# PCB-print.net
KiCad netlist of a schematic drawn in EasyEDA Pro
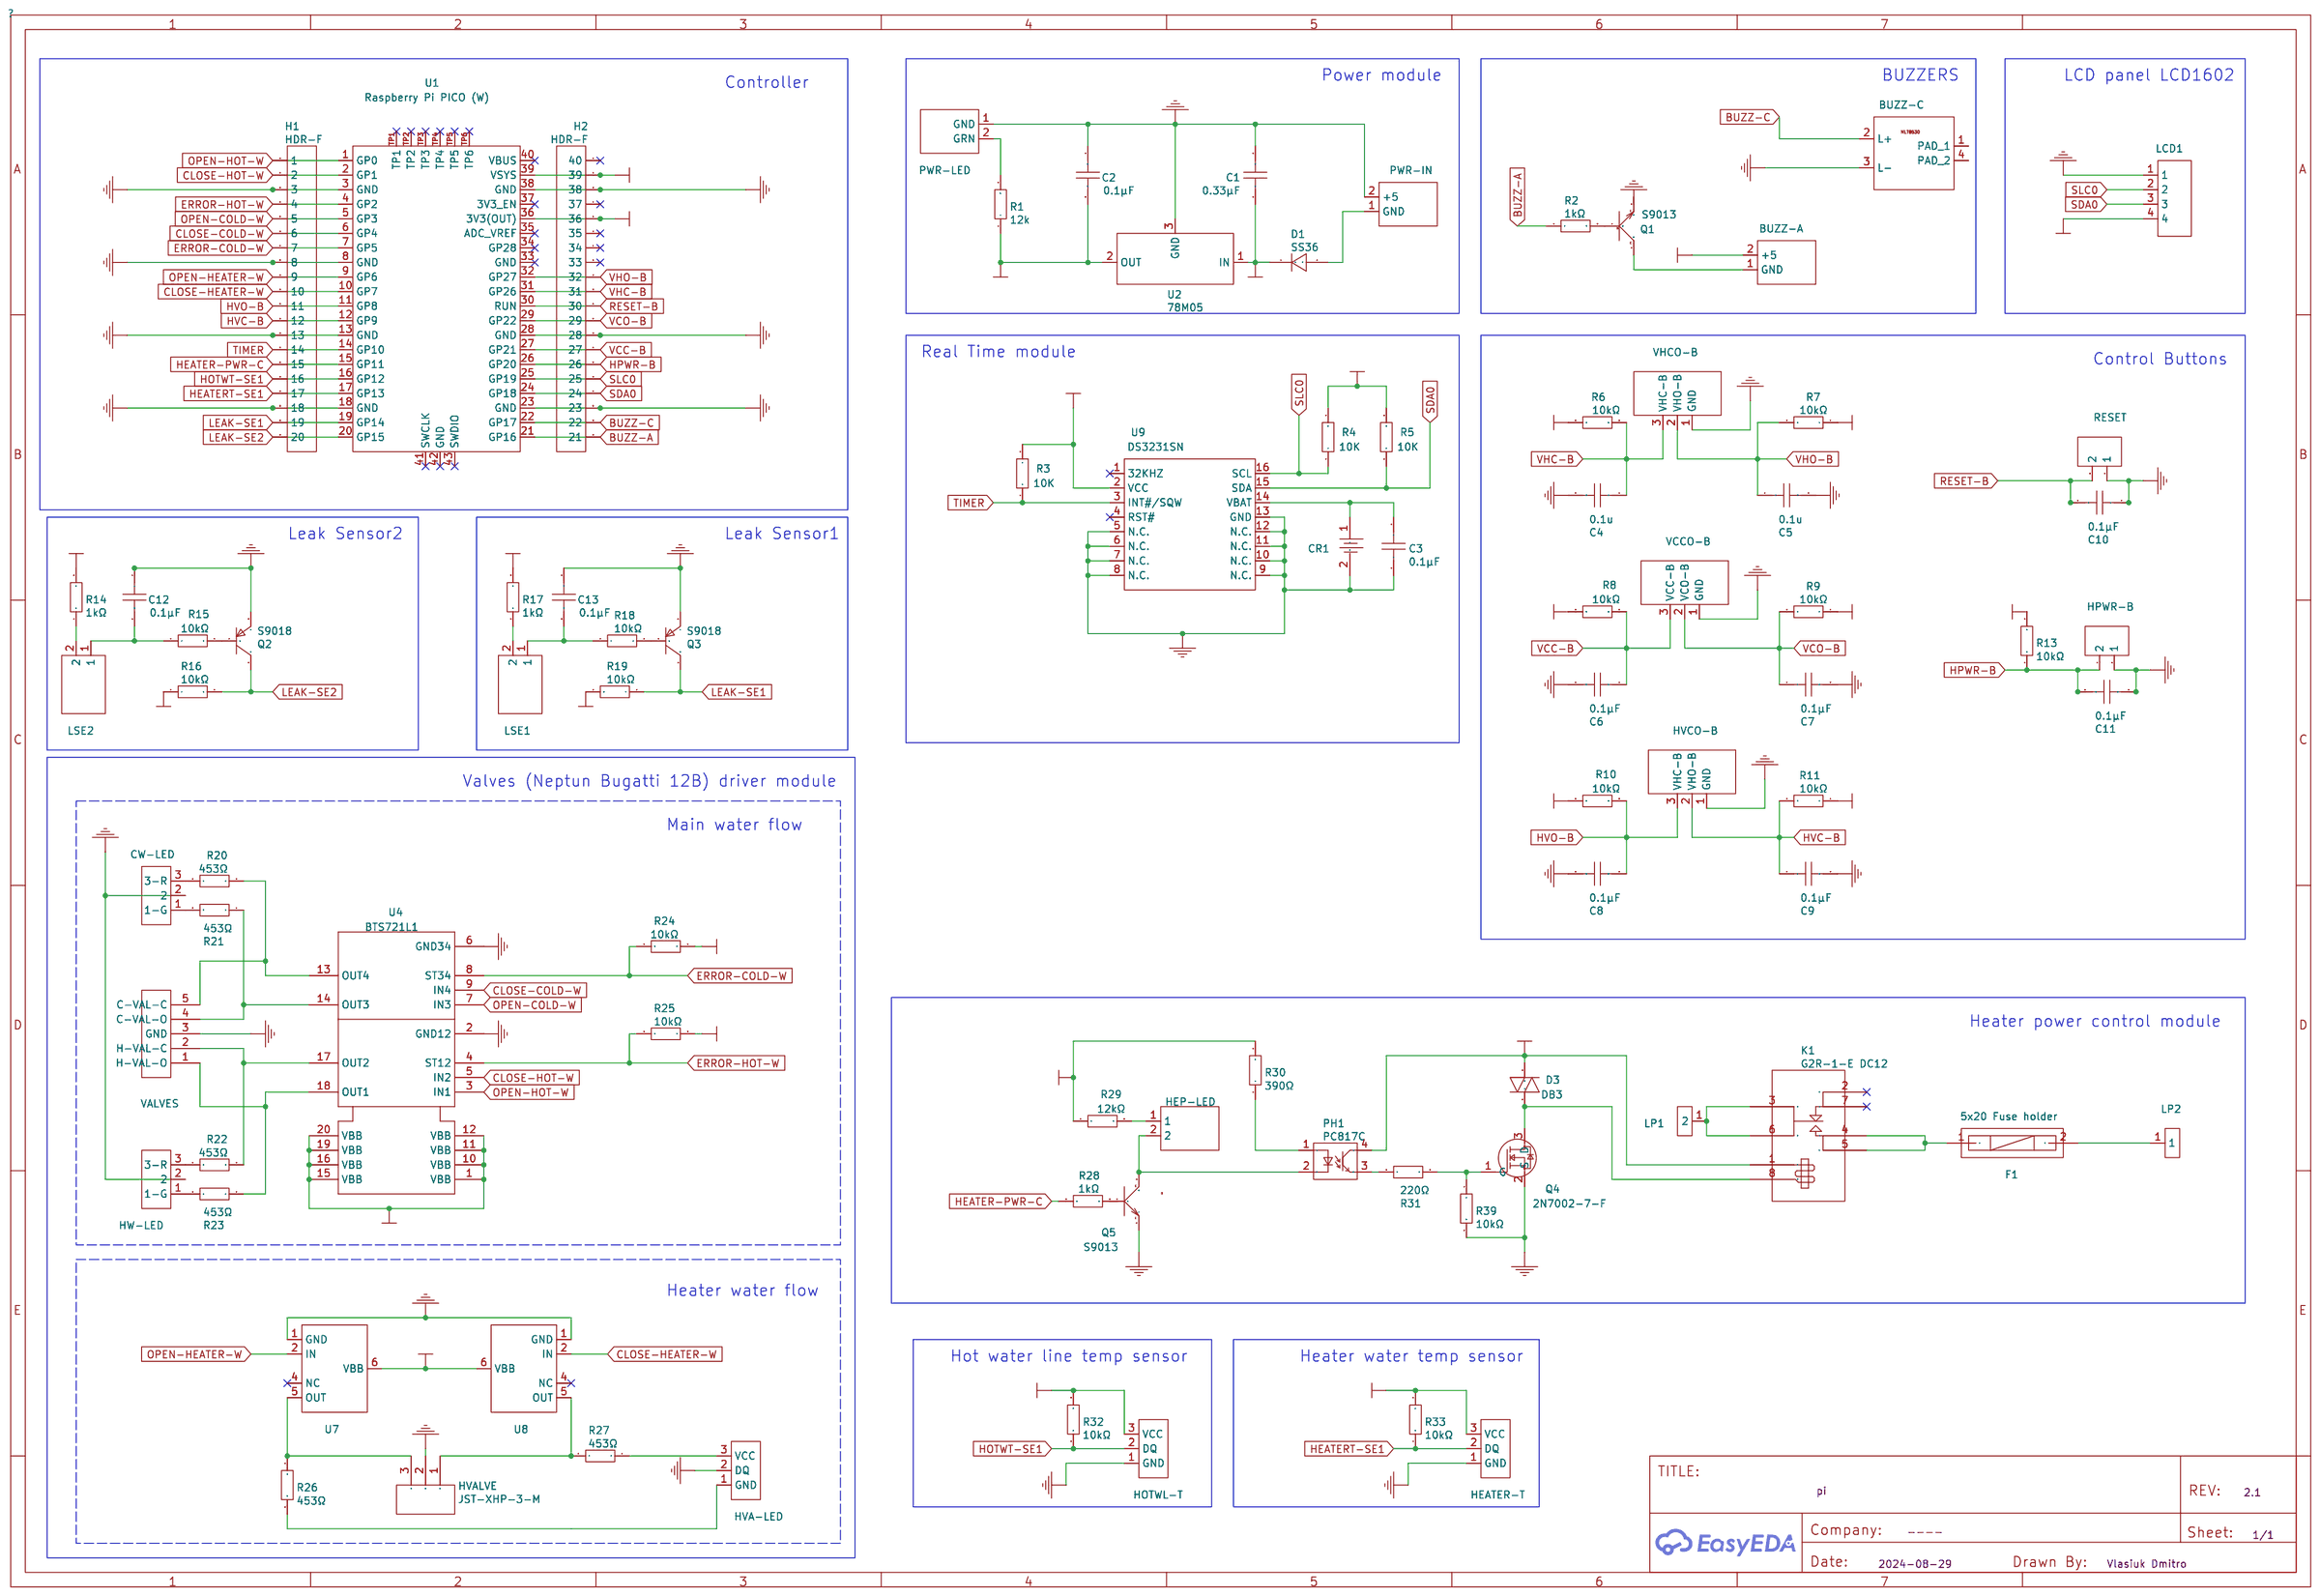
[diagram p0: schematic sheet]

(export (version "E")
  (design (tool "Eeschema 10.0.6"))
  (components
    (comp (ref "BUZZ-A")
      (value "KF2510")
      (fields (field (name "Contributor") "ryan.yulianto"))
      (libsource (lib "easyedapro") (part "KF2510"))
    )
    (comp (ref "BUZZ-C")
      (value "BUZZER-MLT8580_MLT-8530")
      (fields (field (name "Contributor") "Paul Walker"))
      (libsource (lib "easyedapro") (part "BUZZER-MLT8580_MLT-8530"))
    )
    (comp (ref "C1")
      (value "0.33μF")
      (fields (field (name "Manufacturer Part") "C0805X104K050T") (field (name "Contributor") "LCSC"))
      (libsource (lib "easyedapro") (part "0.33μF"))
    )
    (comp (ref "C2")
      (value "0.1μF")
      (fields (field (name "Manufacturer Part") "C0805X104K050T") (field (name "Contributor") "LCSC"))
      (libsource (lib "easyedapro") (part "0.1μF"))
    )
    (comp (ref "C3")
      (value "0.1μF")
      (fields (field (name "Manufacturer Part") "C0805X104K050T") (field (name "Contributor") "LCSC"))
      (libsource (lib "easyedapro") (part "0.1μF"))
    )
    (comp (ref "C4")
      (value "0.1u")
      (fields (field (name "Manufacturer Part") "C0805X104K050T") (field (name "Contributor") "LCSC"))
      (libsource (lib "") (part "0.1u_1"))
    )
    (comp (ref "C5")
      (value "0.1u")
      (fields (field (name "Manufacturer Part") "C0805X104K050T") (field (name "Contributor") "LCSC"))
      (libsource (lib "easyedapro") (part "0.1u"))
    )
    (comp (ref "C6")
      (value "0.1μF")
      (fields (field (name "Manufacturer Part") "C0805X104K050T") (field (name "Contributor") "LCSC"))
      (libsource (lib "") (part "0.1μF_1"))
    )
    (comp (ref "C7")
      (value "0.1μF")
      (fields (field (name "Manufacturer Part") "C0805X104K050T") (field (name "Contributor") "LCSC"))
      (libsource (lib "easyedapro") (part "0.1μF"))
    )
    (comp (ref "C8")
      (value "0.1μF")
      (fields (field (name "Manufacturer Part") "C0805X104K050T") (field (name "Contributor") "LCSC"))
      (libsource (lib "") (part "0.1μF_1"))
    )
    (comp (ref "C9")
      (value "0.1μF")
      (fields (field (name "Manufacturer Part") "C0805X104K050T") (field (name "Contributor") "LCSC"))
      (libsource (lib "easyedapro") (part "0.1μF"))
    )
    (comp (ref "C10")
      (value "0.1μF")
      (fields (field (name "Manufacturer Part") "C0805X104K050T") (field (name "Contributor") "LCSC"))
      (libsource (lib "") (part "0.1μF_1"))
    )
    (comp (ref "C11")
      (value "0.1μF")
      (fields (field (name "Manufacturer Part") "C0805X104K050T") (field (name "Contributor") "LCSC"))
      (libsource (lib "") (part "0.1μF_1"))
    )
    (comp (ref "C12")
      (value "0.1μF")
      (fields (field (name "Manufacturer Part") "C0805X104K050T") (field (name "Contributor") "LCSC"))
      (libsource (lib "easyedapro") (part "0.1μF"))
    )
    (comp (ref "C13")
      (value "0.1μF")
      (fields (field (name "Manufacturer Part") "C0805X104K050T") (field (name "Contributor") "LCSC"))
      (libsource (lib "easyedapro") (part "0.1μF"))
    )
    (comp (ref "CR1")
      (value "KH-CR1220-2")
      (fields (field (name "Manufacturer") "kinghelm(金航标)") (field (name "Contributor") "lcsc"))
      (libsource (lib "easyedapro") (part "KH-CR1220-2"))
    )
    (comp (ref "CW-LED")
      (value "CONN-TH_KF2510-3A")
      (fields (field (name "Manufacturer Part") "KF2510"))
      (libsource (lib "") (part "CONN-TH_KF2510-3A_1"))
    )
    (comp (ref "D1")
      (value "SS36")
      (fields
        (field (name "Manufacturer Part") "SS36-A")
        (field (name "Manufacturer") "FMS(美丽微)")
        (field (name "Contributor") "LCSC")
      )
      (libsource (lib "easyedapro") (part "SS36"))
    )
    (comp (ref "D3")
      (value "DB3")
      (fields (field (name "Contributor") "tyan"))
      (libsource (lib "easyedapro") (part "DB3"))
    )
    (comp (ref "F1")
      (value "5x20 Fuse holder")
      (fields
        (field (name "Manufacturer Part") "5x20 BLX-A型 保险丝支架 XC-7")
        (field (name "Manufacturer") "xcfuse(旭程)")
      )
      (libsource (lib "easyedapro") (part "5x20 Fuse holder"))
    )
    (comp (ref "H1")
      (value "HDR-F")
      (fields (field (name "Contributor") "LCEDA_Lib"))
      (libsource (lib "easyedapro") (part "HDR-F"))
    )
    (comp (ref "H2")
      (value "HDR-F")
      (fields (field (name "Contributor") "LCEDA_Lib"))
      (libsource (lib "") (part "HDR-F_1"))
    )
    (comp (ref "HEATER-T")
      (value "CONN-TH_KF2510-3A")
      (fields (field (name "Manufacturer Part") "KF2510"))
      (libsource (lib "easyedapro") (part "CONN-TH_KF2510-3A"))
    )
    (comp (ref "HEP-LED")
      (value "KF2510")
      (fields (field (name "Contributor") "ryan.yulianto"))
      (libsource (lib "") (part "KF2510_2"))
    )
    (comp (ref "HOTWL-T")
      (value "CONN-TH_KF2510-3A")
      (fields (field (name "Manufacturer Part") "KF2510"))
      (libsource (lib "easyedapro") (part "CONN-TH_KF2510-3A"))
    )
    (comp (ref "HPWR-B")
      (value "HDR-M-2.54_1x2")
      (fields (field (name "Contributor") "QW AS"))
      (libsource (lib "easyedapro") (part "HDR-M-2.54_1x2"))
    )
    (comp (ref "HVA-LED")
      (value "CONN-TH_KF2510-3A")
      (fields (field (name "Manufacturer Part") "KF2510"))
      (libsource (lib "easyedapro") (part "CONN-TH_KF2510-3A"))
    )
    (comp (ref "HVALVE")
      (value "JST-XHP-3-M")
      (fields (field (name "Contributor") "slamdunking"))
      (libsource (lib "easyedapro") (part "JST-XHP-3-M"))
    )
    (comp (ref "HVCO-B")
      (value "HDR-M-2.54_1x3")
      (fields (field (name "Contributor") "Tom Clesius"))
      (libsource (lib "") (part "HDR-M-2.54_1x3_1"))
    )
    (comp (ref "HW-LED")
      (value "CONN-TH_KF2510-3A")
      (fields (field (name "Manufacturer Part") "KF2510"))
      (libsource (lib "") (part "CONN-TH_KF2510-3A_2"))
    )
    (comp (ref "K1") (value "G2R-1-E DC12") (libsource (lib "easyedapro") (part "G2R-1-E DC12")))
    (comp (ref "LCD1")
      (value "TERMINAL_KF2510-4A-")
      (fields (field (name "Manufacturer Part") "KF2510-4A") (field (name "Contributor") "Mikhail Malyshev"))
      (libsource (lib "easyedapro") (part "TERMINAL_KF2510-4A-"))
    )
    (comp (ref "LP1")
      (value "PCB Spade Terminal - 5.08")
      (fields (field (name "Manufacturer Part") "?") (field (name "Contributor") "themongrel"))
      (libsource (lib "") (part "PCB Spade Terminal - 5.08_1"))
    )
    (comp (ref "LP2")
      (value "PCB Spade Terminal - 5.08")
      (fields (field (name "Manufacturer Part") "?") (field (name "Contributor") "themongrel"))
      (libsource (lib "easyedapro") (part "PCB Spade Terminal - 5.08"))
    )
    (comp (ref "LSE1")
      (value "KF2510")
      (fields (field (name "Contributor") "ryan.yulianto"))
      (libsource (lib "") (part "KF2510_1"))
    )
    (comp (ref "LSE2")
      (value "KF2510")
      (fields (field (name "Contributor") "ryan.yulianto"))
      (libsource (lib "") (part "KF2510_1"))
    )
    (comp (ref "PH1")
      (value "PC817C")
      (fields (field (name "Contributor") "RaspAutomacao"))
      (libsource (lib "easyedapro") (part "PC817C"))
    )
    (comp (ref "PWR-IN")
      (value "KF2510")
      (fields (field (name "Contributor") "ryan.yulianto"))
      (libsource (lib "easyedapro") (part "KF2510"))
    )
    (comp (ref "PWR-LED")
      (value "KF2510")
      (fields (field (name "Contributor") "ryan.yulianto"))
      (libsource (lib "") (part "KF2510_3"))
    )
    (comp (ref "Q1") (value "S9013") (libsource (lib "easyedapro") (part "S9013")))
    (comp (ref "Q2")
      (value "S9018")
      (fields (field (name "Manufacturer") "晶导微电子") (field (name "Contributor") "lcsc"))
      (libsource (lib "easyedapro") (part "S9018"))
    )
    (comp (ref "Q3")
      (value "S9018")
      (fields (field (name "Manufacturer") "晶导微电子") (field (name "Contributor") "lcsc"))
      (libsource (lib "easyedapro") (part "S9018"))
    )
    (comp (ref "Q4")
      (value "2N7002-7-F")
      (fields (field (name "Manufacturer") "Diodes Incorporated") (field (name "Contributor") "ewick91"))
      (libsource (lib "easyedapro") (part "2N7002-7-F"))
    )
    (comp (ref "Q5") (value "S9013") (libsource (lib "") (part "S9013_1")))
    (comp (ref "R1")
      (value "12k")
      (fields (field (name "Contributor") "dulajekanayake123"))
      (libsource (lib "easyedapro") (part "150"))
    )
    (comp (ref "R2")
      (value "1kΩ")
      (fields
        (field (name "Manufacturer Part") "1% High Precision SMD Resistor")
        (field (name "Contributor") "dulajekanayake123")
      )
      (libsource (lib "") (part "1kΩ_1"))
    )
    (comp (ref "R3")
      (value "10К")
      (fields (field (name "Contributor") "dulajekanayake123"))
      (libsource (lib "easyedapro") (part "10К"))
    )
    (comp (ref "R4")
      (value "10К")
      (fields (field (name "Contributor") "dulajekanayake123"))
      (libsource (lib "easyedapro") (part "10К"))
    )
    (comp (ref "R5")
      (value "10К")
      (fields (field (name "Contributor") "dulajekanayake123"))
      (libsource (lib "easyedapro") (part "10К"))
    )
    (comp (ref "R6")
      (value "10kΩ")
      (fields
        (field (name "Manufacturer Part") "1% High Precision SMD Resistor")
        (field (name "Contributor") "dulajekanayake123")
      )
      (libsource (lib "easyedapro") (part "10kΩ"))
    )
    (comp (ref "R7")
      (value "10kΩ")
      (fields
        (field (name "Manufacturer Part") "1% High Precision SMD Resistor")
        (field (name "Contributor") "dulajekanayake123")
      )
      (libsource (lib "") (part "10kΩ_1"))
    )
    (comp (ref "R8")
      (value "10kΩ")
      (fields
        (field (name "Manufacturer Part") "1% High Precision SMD Resistor")
        (field (name "Contributor") "dulajekanayake123")
      )
      (libsource (lib "easyedapro") (part "10kΩ"))
    )
    (comp (ref "R9")
      (value "10kΩ")
      (fields
        (field (name "Manufacturer Part") "1% High Precision SMD Resistor")
        (field (name "Contributor") "dulajekanayake123")
      )
      (libsource (lib "") (part "10kΩ_1"))
    )
    (comp (ref "R10")
      (value "10kΩ")
      (fields
        (field (name "Manufacturer Part") "1% High Precision SMD Resistor")
        (field (name "Contributor") "dulajekanayake123")
      )
      (libsource (lib "easyedapro") (part "10kΩ"))
    )
    (comp (ref "R11")
      (value "10kΩ")
      (fields
        (field (name "Manufacturer Part") "1% High Precision SMD Resistor")
        (field (name "Contributor") "dulajekanayake123")
      )
      (libsource (lib "") (part "10kΩ_1"))
    )
    (comp (ref "R13")
      (value "10kΩ")
      (fields
        (field (name "Manufacturer Part") "1% High Precision SMD Resistor")
        (field (name "Contributor") "dulajekanayake123")
      )
      (libsource (lib "") (part "10kΩ_3"))
    )
    (comp (ref "R14")
      (value "1kΩ")
      (fields
        (field (name "Manufacturer Part") "1% High Precision SMD Resistor")
        (field (name "Contributor") "dulajekanayake123")
      )
      (libsource (lib "easyedapro") (part "1kΩ"))
    )
    (comp (ref "R15")
      (value "10kΩ")
      (fields
        (field (name "Manufacturer Part") "1% High Precision SMD Resistor")
        (field (name "Contributor") "dulajekanayake123")
      )
      (libsource (lib "easyedapro") (part "10kΩ"))
    )
    (comp (ref "R16")
      (value "10kΩ")
      (fields
        (field (name "Manufacturer Part") "1% High Precision SMD Resistor")
        (field (name "Contributor") "dulajekanayake123")
      )
      (libsource (lib "easyedapro") (part "10kΩ"))
    )
    (comp (ref "R17")
      (value "1kΩ")
      (fields
        (field (name "Manufacturer Part") "1% High Precision SMD Resistor")
        (field (name "Contributor") "dulajekanayake123")
      )
      (libsource (lib "easyedapro") (part "1kΩ"))
    )
    (comp (ref "R18")
      (value "10kΩ")
      (fields
        (field (name "Manufacturer Part") "1% High Precision SMD Resistor")
        (field (name "Contributor") "dulajekanayake123")
      )
      (libsource (lib "easyedapro") (part "10kΩ"))
    )
    (comp (ref "R19")
      (value "10kΩ")
      (fields
        (field (name "Manufacturer Part") "1% High Precision SMD Resistor")
        (field (name "Contributor") "dulajekanayake123")
      )
      (libsource (lib "") (part "10kΩ_1"))
    )
    (comp (ref "R20")
      (value "453Ω")
      (fields
        (field (name "Manufacturer Part") "1% High Precision SMD Resistor")
        (field (name "Contributor") "dulajekanayake123")
      )
      (libsource (lib "") (part "453Ω_1"))
    )
    (comp (ref "R21")
      (value "453Ω")
      (fields
        (field (name "Manufacturer Part") "1% High Precision SMD Resistor")
        (field (name "Contributor") "dulajekanayake123")
      )
      (libsource (lib "") (part "453Ω_2"))
    )
    (comp (ref "R22")
      (value "453Ω")
      (fields
        (field (name "Manufacturer Part") "1% High Precision SMD Resistor")
        (field (name "Contributor") "dulajekanayake123")
      )
      (libsource (lib "") (part "453Ω_1"))
    )
    (comp (ref "R23")
      (value "453Ω")
      (fields
        (field (name "Manufacturer Part") "1% High Precision SMD Resistor")
        (field (name "Contributor") "dulajekanayake123")
      )
      (libsource (lib "") (part "453Ω_2"))
    )
    (comp (ref "R24")
      (value "10kΩ")
      (fields
        (field (name "Manufacturer Part") "1% High Precision SMD Resistor")
        (field (name "Contributor") "dulajekanayake123")
      )
      (libsource (lib "easyedapro") (part "10kΩ"))
    )
    (comp (ref "R25")
      (value "10kΩ")
      (fields
        (field (name "Manufacturer Part") "1% High Precision SMD Resistor")
        (field (name "Contributor") "dulajekanayake123")
      )
      (libsource (lib "easyedapro") (part "10kΩ"))
    )
    (comp (ref "R26")
      (value "453Ω")
      (fields
        (field (name "Manufacturer Part") "1% High Precision SMD Resistor")
        (field (name "Contributor") "dulajekanayake123")
      )
      (libsource (lib "easyedapro") (part "453Ω"))
    )
    (comp (ref "R27")
      (value "453Ω")
      (fields
        (field (name "Manufacturer Part") "1% High Precision SMD Resistor")
        (field (name "Contributor") "dulajekanayake123")
      )
      (libsource (lib "") (part "453Ω_2"))
    )
    (comp (ref "R28")
      (value "1kΩ")
      (fields
        (field (name "Manufacturer Part") "1% High Precision SMD Resistor")
        (field (name "Contributor") "dulajekanayake123")
      )
      (libsource (lib "") (part "1kΩ_1"))
    )
    (comp (ref "R29")
      (value "12kΩ")
      (fields
        (field (name "Manufacturer Part") "1% High Precision SMD Resistor")
        (field (name "Contributor") "dulajekanayake123")
      )
      (libsource (lib "easyedapro") (part "150kΩ"))
    )
    (comp (ref "R30")
      (value "390Ω")
      (fields (field (name "Manufacturer Part") "?"))
      (libsource (lib "easyedapro") (part "390Ω"))
    )
    (comp (ref "R31")
      (value "220Ω")
      (fields (field (name "Manufacturer Part") "?"))
      (libsource (lib "easyedapro") (part "220Ω"))
    )
    (comp (ref "R32")
      (value "10kΩ")
      (fields
        (field (name "Manufacturer Part") "1% High Precision SMD Resistor")
        (field (name "Contributor") "dulajekanayake123")
      )
      (libsource (lib "") (part "10kΩ_3"))
    )
    (comp (ref "R33")
      (value "10kΩ")
      (fields
        (field (name "Manufacturer Part") "1% High Precision SMD Resistor")
        (field (name "Contributor") "dulajekanayake123")
      )
      (libsource (lib "") (part "10kΩ_3"))
    )
    (comp (ref "R39")
      (value "10kΩ")
      (fields (field (name "Manufacturer Part") "?"))
      (libsource (lib "") (part "10kΩ_2"))
    )
    (comp (ref "RESET")
      (value "HDR-M-2.54_1x2")
      (fields (field (name "Contributor") "QW AS"))
      (libsource (lib "easyedapro") (part "HDR-M-2.54_1x2"))
    )
    (comp (ref "U1")
      (value "Raspberry Pi PICO (W)")
      (fields
        (field (name "Manufacturer Part") "PICO")
        (field (name "Manufacturer") "Raspberry Pi(树莓派)")
        (field (name "Contributor") "lcsc")
      )
      (libsource (lib "easyedapro") (part "Raspberry Pi PICO (W)"))
    )
    (comp (ref "U2")
      (value "78M05")
      (fields (field (name "Contributor") "lcsc"))
      (libsource (lib "easyedapro") (part "78M05"))
    )
    (comp (ref "U4")
      (value "BTS721L1")
      (fields (field (name "Manufacturer") "BTS721L1 Infineon"))
      (libsource (lib "easyedapro") (part "BTS721L1"))
    )
    (comp (ref "U7")
      (value "BTS452TATMA1_C5309408")
      (fields
        (field (name "Manufacturer Part") "BTS452TATMA1")
        (field (name "Manufacturer") "Infineon(英飞凌)")
        (field (name "Contributor") "lcsc")
      )
      (libsource (lib "easyedapro") (part "BTS452TATMA1_C5309408"))
    )
    (comp (ref "U8")
      (value "BTS452TATMA1_C5309408")
      (fields
        (field (name "Manufacturer Part") "BTS452TATMA1")
        (field (name "Manufacturer") "Infineon(英飞凌)")
        (field (name "Contributor") "lcsc")
      )
      (libsource (lib "") (part "BTS452TATMA1_C5309408_1"))
    )
    (comp (ref "U9")
      (value "DS3231SN")
      (fields
        (field (name "Manufacturer Part") "DS3231SN#")
        (field (name "Manufacturer") "ADI(亚德诺)/MAXIM(美信)")
        (field (name "Contributor") "lcsc")
      )
      (libsource (lib "easyedapro") (part "DS3231SN"))
    )
    (comp (ref "VALVES")
      (value "JST-XHP-5-M")
      (fields (field (name "Contributor") "slamdunking"))
      (libsource (lib "easyedapro") (part "JST-XHP-5-M"))
    )
    (comp (ref "VCCO-B")
      (value "HDR-M-2.54_1x3")
      (fields (field (name "Contributor") "Tom Clesius"))
      (libsource (lib "easyedapro") (part "HDR-M-2.54_1x3"))
    )
    (comp (ref "VHCO-B")
      (value "HDR-M-2.54_1x3")
      (fields (field (name "Contributor") "Tom Clesius"))
      (libsource (lib "") (part "HDR-M-2.54_1x3_1"))
    )
  )
  (nets
    (net (code "1") (name "+3.3V") (class "Default")
      (node (ref "H2") (pin "5") (pinfunction "36_5") (pintype "unspecified"))
      (node (ref "HEATER-T") (pin "3") (pinfunction "VCC_3") (pintype "unspecified"))
      (node (ref "HOTWL-T") (pin "3") (pinfunction "VCC_3") (pintype "unspecified"))
      (node (ref "R10") (pin "1") (pinfunction "1_1") (pintype "unspecified"))
      (node (ref "R11") (pin "1") (pinfunction "1_1") (pintype "unspecified"))
      (node (ref "R13") (pin "2") (pinfunction "2_2") (pintype "unspecified"))
      (node (ref "R16") (pin "1") (pinfunction "1_1") (pintype "unspecified"))
      (node (ref "R19") (pin "2") (pinfunction "2_2") (pintype "unspecified"))
      (node (ref "R24") (pin "2") (pinfunction "2_2") (pintype "unspecified"))
      (node (ref "R25") (pin "2") (pinfunction "2_2") (pintype "unspecified"))
      (node (ref "R3") (pin "2") (pinfunction "2_2") (pintype "unspecified"))
      (node (ref "R32") (pin "2") (pinfunction "2_2") (pintype "unspecified"))
      (node (ref "R33") (pin "2") (pinfunction "2_2") (pintype "unspecified"))
      (node (ref "R4") (pin "2") (pinfunction "2_2") (pintype "unspecified"))
      (node (ref "R5") (pin "2") (pinfunction "2_2") (pintype "unspecified"))
      (node (ref "R6") (pin "1") (pinfunction "1_1") (pintype "unspecified"))
      (node (ref "R7") (pin "1") (pinfunction "1_1") (pintype "unspecified"))
      (node (ref "R8") (pin "1") (pinfunction "1_1") (pintype "unspecified"))
      (node (ref "R9") (pin "1") (pinfunction "1_1") (pintype "unspecified"))
      (node (ref "U1") (pin "36") (pinfunction "3V3(OUT)_36") (pintype "unspecified"))
      (node (ref "U9") (pin "2") (pinfunction "VCC_2") (pintype "unspecified"))
    )
    (net (code "2") (name "+5V") (class "Default")
      (node (ref "BUZZ-A") (pin "2") (pinfunction "+5_2") (pintype "unspecified"))
      (node (ref "C2") (pin "2") (pinfunction "2_2") (pintype "unspecified"))
      (node (ref "H2") (pin "2") (pinfunction "39_2") (pintype "unspecified"))
      (node (ref "LCD1") (pin "4") (pinfunction "4_4") (pintype "unspecified"))
      (node (ref "R1") (pin "1") (pinfunction "1_1") (pintype "unspecified"))
      (node (ref "R14") (pin "2") (pinfunction "2_2") (pintype "unspecified"))
      (node (ref "R17") (pin "2") (pinfunction "2_2") (pintype "unspecified"))
      (node (ref "R29") (pin "1") (pinfunction "1_1") (pintype "unspecified"))
      (node (ref "R30") (pin "2") (pinfunction "2_2") (pintype "unspecified"))
      (node (ref "U1") (pin "39") (pinfunction "VSYS_39") (pintype "unspecified"))
      (node (ref "U2") (pin "2") (pinfunction "OUT_2") (pintype "unspecified"))
    )
    (net (code "3") (name "+12V") (class "Default")
      (node (ref "C1") (pin "2") (pinfunction "2_2") (pintype "unspecified"))
      (node (ref "D1") (pin "1") (pinfunction "1_1") (pintype "unspecified"))
      (node (ref "D3") (pin "2") (pinfunction "2_2") (pintype "unspecified"))
      (node (ref "K1") (pin "1") (pinfunction "1_1") (pintype "input"))
      (node (ref "PH1") (pin "4") (pinfunction "4_4") (pintype "unspecified"))
      (node (ref "U2") (pin "1") (pinfunction "IN_1") (pintype "unspecified"))
      (node (ref "U4") (pin "1") (pinfunction "VBB_1") (pintype "unspecified"))
      (node (ref "U4") (pin "10") (pinfunction "VBB_10") (pintype "unspecified"))
      (node (ref "U4") (pin "11") (pinfunction "VBB_11") (pintype "unspecified"))
      (node (ref "U4") (pin "12") (pinfunction "VBB_12") (pintype "unspecified"))
      (node (ref "U4") (pin "15") (pinfunction "VBB_15") (pintype "unspecified"))
      (node (ref "U4") (pin "16") (pinfunction "VBB_16") (pintype "unspecified"))
      (node (ref "U4") (pin "19") (pinfunction "VBB_19") (pintype "unspecified"))
      (node (ref "U4") (pin "20") (pinfunction "VBB_20") (pintype "unspecified"))
      (node (ref "U7") (pin "6") (pinfunction "VBB_6") (pintype "unspecified"))
      (node (ref "U8") (pin "6") (pinfunction "VBB_6") (pintype "unspecified"))
    )
    (net (code "4") (name "BUZZ-A") (class "Default")
      (node (ref "H2") (pin "20") (pinfunction "21_20") (pintype "unspecified"))
      (node (ref "R2") (pin "1") (pinfunction "1_1") (pintype "unspecified"))
      (node (ref "U1") (pin "21") (pinfunction "GP16_21") (pintype "unspecified"))
    )
    (net (code "5") (name "BUZZ-C") (class "Default")
      (node (ref "BUZZ-C") (pin "2") (pinfunction "L+_2") (pintype "unspecified"))
      (node (ref "H2") (pin "19") (pinfunction "22_19") (pintype "unspecified"))
      (node (ref "U1") (pin "22") (pinfunction "GP17_22") (pintype "unspecified"))
    )
    (net (code "6") (name "CLOSE-COLD-W") (class "Default")
      (node (ref "H1") (pin "6") (pinfunction "6_6") (pintype "unspecified"))
      (node (ref "U1") (pin "6") (pinfunction "GP4_6") (pintype "unspecified"))
      (node (ref "U4") (pin "9") (pinfunction "IN4_9") (pintype "input"))
    )
    (net (code "7") (name "CLOSE-HEATER-W") (class "Default")
      (node (ref "H1") (pin "10") (pinfunction "10_10") (pintype "unspecified"))
      (node (ref "U1") (pin "10") (pinfunction "GP7_10") (pintype "unspecified"))
      (node (ref "U8") (pin "2") (pinfunction "IN_2") (pintype "unspecified"))
    )
    (net (code "8") (name "CLOSE-HOT-W") (class "Default")
      (node (ref "H1") (pin "2") (pinfunction "2_2") (pintype "unspecified"))
      (node (ref "U1") (pin "2") (pinfunction "GP1_2") (pintype "unspecified"))
      (node (ref "U4") (pin "5") (pinfunction "IN2_5") (pintype "input"))
    )
    (net (code "9") (name "ERROR-COLD-W") (class "Default")
      (node (ref "H1") (pin "7") (pinfunction "7_7") (pintype "unspecified"))
      (node (ref "R24") (pin "1") (pinfunction "1_1") (pintype "unspecified"))
      (node (ref "U1") (pin "7") (pinfunction "GP5_7") (pintype "unspecified"))
      (node (ref "U4") (pin "8") (pinfunction "ST34_8") (pintype "unspecified"))
    )
    (net (code "10") (name "ERROR-HOT-W") (class "Default")
      (node (ref "H1") (pin "4") (pinfunction "4_4") (pintype "unspecified"))
      (node (ref "R25") (pin "1") (pinfunction "1_1") (pintype "unspecified"))
      (node (ref "U1") (pin "4") (pinfunction "GP2_4") (pintype "unspecified"))
      (node (ref "U4") (pin "4") (pinfunction "ST12_4") (pintype "unspecified"))
    )
    (net (code "11") (name "GND") (class "Default")
      (node (ref "BUZZ-C") (pin "3") (pinfunction "L-_3") (pintype "unspecified"))
      (node (ref "C1") (pin "1") (pinfunction "1_1") (pintype "unspecified"))
      (node (ref "C10") (pin "1") (pinfunction "1_1") (pintype "unspecified"))
      (node (ref "C11") (pin "1") (pinfunction "1_1") (pintype "unspecified"))
      (node (ref "C12") (pin "1") (pinfunction "1_1") (pintype "unspecified"))
      (node (ref "C13") (pin "1") (pinfunction "1_1") (pintype "unspecified"))
      (node (ref "C2") (pin "1") (pinfunction "1_1") (pintype "unspecified"))
      (node (ref "C3") (pin "2") (pinfunction "2_2") (pintype "unspecified"))
      (node (ref "C4") (pin "2") (pinfunction "2_2") (pintype "unspecified"))
      (node (ref "C5") (pin "2") (pinfunction "2_2") (pintype "unspecified"))
      (node (ref "C6") (pin "2") (pinfunction "2_2") (pintype "unspecified"))
      (node (ref "C7") (pin "2") (pinfunction "2_2") (pintype "unspecified"))
      (node (ref "C8") (pin "2") (pinfunction "2_2") (pintype "unspecified"))
      (node (ref "C9") (pin "2") (pinfunction "2_2") (pintype "unspecified"))
      (node (ref "CR1") (pin "2") (pinfunction "2_2") (pintype "input"))
      (node (ref "CW-LED") (pin "2") (pinfunction "2_2") (pintype "unspecified"))
      (node (ref "H1") (pin "13") (pinfunction "13_13") (pintype "unspecified"))
      (node (ref "H1") (pin "18") (pinfunction "18_18") (pintype "unspecified"))
      (node (ref "H1") (pin "3") (pinfunction "3_3") (pintype "unspecified"))
      (node (ref "H1") (pin "8") (pinfunction "8_8") (pintype "unspecified"))
      (node (ref "H2") (pin "13") (pinfunction "28_13") (pintype "unspecified"))
      (node (ref "H2") (pin "18") (pinfunction "23_18") (pintype "unspecified"))
      (node (ref "H2") (pin "3") (pinfunction "38_3") (pintype "unspecified"))
      (node (ref "HEATER-T") (pin "1") (pinfunction "GND_1") (pintype "unspecified"))
      (node (ref "HOTWL-T") (pin "1") (pinfunction "GND_1") (pintype "unspecified"))
      (node (ref "HPWR-B") (pin "1") (pinfunction "1_1") (pintype "unspecified"))
      (node (ref "HVA-LED") (pin "2") (pinfunction "DQ_2") (pintype "unspecified"))
      (node (ref "HVALVE") (pin "2") (pinfunction "2_2") (pintype "unspecified"))
      (node (ref "HVCO-B") (pin "1") (pinfunction "GND_1") (pintype "unspecified"))
      (node (ref "HW-LED") (pin "2") (pinfunction "2_2") (pintype "unspecified"))
      (node (ref "LCD1") (pin "1") (pinfunction "1_1") (pintype "unspecified"))
      (node (ref "PWR-IN") (pin "2") (pinfunction "+5_2") (pintype "unspecified"))
      (node (ref "PWR-LED") (pin "1") (pinfunction "GND_1") (pintype "unspecified"))
      (node (ref "Q1") (pin "2") (pinfunction "E_2") (pintype "unspecified"))
      (node (ref "Q2") (pin "2") (pinfunction "E_2") (pintype "input"))
      (node (ref "Q3") (pin "2") (pinfunction "E_2") (pintype "input"))
      (node (ref "Q4") (pin "2") (pinfunction "S_2") (pintype "bidirectional"))
      (node (ref "Q5") (pin "2") (pinfunction "E_2") (pintype "unspecified"))
      (node (ref "R39") (pin "2") (pinfunction "2_2") (pintype "unspecified"))
      (node (ref "RESET") (pin "1") (pinfunction "1_1") (pintype "unspecified"))
      (node (ref "U1") (pin "13") (pinfunction "GND_13") (pintype "unspecified"))
      (node (ref "U1") (pin "18") (pinfunction "GND_18") (pintype "unspecified"))
      (node (ref "U1") (pin "23") (pinfunction "GND_23") (pintype "unspecified"))
      (node (ref "U1") (pin "28") (pinfunction "GND_28") (pintype "unspecified"))
      (node (ref "U1") (pin "3") (pinfunction "GND_3") (pintype "unspecified"))
      (node (ref "U1") (pin "38") (pinfunction "GND_38") (pintype "unspecified"))
      (node (ref "U1") (pin "8") (pinfunction "GND_8") (pintype "unspecified"))
      (node (ref "U2") (pin "3") (pinfunction "GND_3") (pintype "unspecified"))
      (node (ref "U4") (pin "2") (pinfunction "GND12_2") (pintype "unspecified"))
      (node (ref "U4") (pin "6") (pinfunction "GND34_6") (pintype "unspecified"))
      (node (ref "U7") (pin "1") (pinfunction "GND_1") (pintype "unspecified"))
      (node (ref "U8") (pin "1") (pinfunction "GND_1") (pintype "unspecified"))
      (node (ref "U9") (pin "10") (pinfunction "N.C._10") (pintype "unspecified"))
      (node (ref "U9") (pin "11") (pinfunction "N.C._11") (pintype "unspecified"))
      (node (ref "U9") (pin "12") (pinfunction "N.C._12") (pintype "unspecified"))
      (node (ref "U9") (pin "13") (pinfunction "GND_13") (pintype "unspecified"))
      (node (ref "U9") (pin "5") (pinfunction "N.C._5") (pintype "unspecified"))
      (node (ref "U9") (pin "6") (pinfunction "N.C._6") (pintype "unspecified"))
      (node (ref "U9") (pin "7") (pinfunction "N.C._7") (pintype "unspecified"))
      (node (ref "U9") (pin "8") (pinfunction "N.C._8") (pintype "unspecified"))
      (node (ref "U9") (pin "9") (pinfunction "N.C._9") (pintype "unspecified"))
      (node (ref "VALVES") (pin "3") (pinfunction "GND_3") (pintype "output"))
      (node (ref "VCCO-B") (pin "1") (pinfunction "GND_1") (pintype "unspecified"))
      (node (ref "VHCO-B") (pin "1") (pinfunction "GND_1") (pintype "unspecified"))
    )
    (net (code "12") (name "HEATER-PWR-C") (class "Default")
      (node (ref "H1") (pin "15") (pinfunction "15_15") (pintype "unspecified"))
      (node (ref "R28") (pin "1") (pinfunction "1_1") (pintype "unspecified"))
      (node (ref "U1") (pin "15") (pinfunction "GP11_15") (pintype "unspecified"))
    )
    (net (code "13") (name "HEATERT-SE1") (class "Default")
      (node (ref "H1") (pin "17") (pinfunction "17_17") (pintype "unspecified"))
      (node (ref "HEATER-T") (pin "2") (pinfunction "DQ_2") (pintype "unspecified"))
      (node (ref "R33") (pin "1") (pinfunction "1_1") (pintype "unspecified"))
      (node (ref "U1") (pin "17") (pinfunction "GP13_17") (pintype "unspecified"))
    )
    (net (code "14") (name "HOTWT-SE1") (class "Default")
      (node (ref "H1") (pin "16") (pinfunction "16_16") (pintype "unspecified"))
      (node (ref "HOTWL-T") (pin "2") (pinfunction "DQ_2") (pintype "unspecified"))
      (node (ref "R32") (pin "1") (pinfunction "1_1") (pintype "unspecified"))
      (node (ref "U1") (pin "16") (pinfunction "GP12_16") (pintype "unspecified"))
    )
    (net (code "15") (name "HPWR-B") (class "Default")
      (node (ref "C11") (pin "2") (pinfunction "2_2") (pintype "unspecified"))
      (node (ref "H2") (pin "15") (pinfunction "26_15") (pintype "unspecified"))
      (node (ref "HPWR-B") (pin "2") (pinfunction "2_2") (pintype "unspecified"))
      (node (ref "R13") (pin "1") (pinfunction "1_1") (pintype "unspecified"))
      (node (ref "U1") (pin "26") (pinfunction "GP20_26") (pintype "unspecified"))
    )
    (net (code "16") (name "HVC-B") (class "Default")
      (node (ref "C9") (pin "1") (pinfunction "1_1") (pintype "unspecified"))
      (node (ref "H1") (pin "12") (pinfunction "12_12") (pintype "unspecified"))
      (node (ref "HVCO-B") (pin "2") (pinfunction "VHO-B_2") (pintype "unspecified"))
      (node (ref "R11") (pin "2") (pinfunction "2_2") (pintype "unspecified"))
      (node (ref "U1") (pin "12") (pinfunction "GP9_12") (pintype "unspecified"))
    )
    (net (code "17") (name "HVO-B") (class "Default")
      (node (ref "C8") (pin "1") (pinfunction "1_1") (pintype "unspecified"))
      (node (ref "H1") (pin "11") (pinfunction "11_11") (pintype "unspecified"))
      (node (ref "HVCO-B") (pin "3") (pinfunction "VHC-B_3") (pintype "unspecified"))
      (node (ref "R10") (pin "2") (pinfunction "2_2") (pintype "unspecified"))
      (node (ref "U1") (pin "11") (pinfunction "GP8_11") (pintype "unspecified"))
    )
    (net (code "18") (name "LEAK-SE1") (class "Default")
      (node (ref "H1") (pin "19") (pinfunction "19_19") (pintype "unspecified"))
      (node (ref "Q3") (pin "3") (pinfunction "C_3") (pintype "input"))
      (node (ref "R19") (pin "1") (pinfunction "1_1") (pintype "unspecified"))
      (node (ref "U1") (pin "19") (pinfunction "GP14_19") (pintype "unspecified"))
    )
    (net (code "19") (name "LEAK-SE2") (class "Default")
      (node (ref "H1") (pin "20") (pinfunction "20_20") (pintype "unspecified"))
      (node (ref "Q2") (pin "3") (pinfunction "C_3") (pintype "input"))
      (node (ref "R16") (pin "2") (pinfunction "2_2") (pintype "unspecified"))
      (node (ref "U1") (pin "20") (pinfunction "GP15_20") (pintype "unspecified"))
    )
    (net (code "20") (name "Net-(BUZZ-A-GND)") (class "Default")
      (node (ref "BUZZ-A") (pin "1") (pinfunction "GND_1") (pintype "unspecified"))
      (node (ref "Q1") (pin "3") (pinfunction "C_3") (pintype "unspecified"))
    )
    (net (code "21") (name "Net-(C12-Pad2)") (class "Default")
      (node (ref "C12") (pin "2") (pinfunction "2_2") (pintype "unspecified"))
      (node (ref "LSE2") (pin "1") (pinfunction "1_1") (pintype "unspecified"))
      (node (ref "R15") (pin "1") (pinfunction "1_1") (pintype "unspecified"))
    )
    (net (code "22") (name "Net-(C13-Pad2)") (class "Default")
      (node (ref "C13") (pin "2") (pinfunction "2_2") (pintype "unspecified"))
      (node (ref "LSE1") (pin "1") (pinfunction "1_1") (pintype "unspecified"))
      (node (ref "R18") (pin "1") (pinfunction "1_1") (pintype "unspecified"))
    )
    (net (code "23") (name "Net-(CW-LED-1-G)") (class "Default")
      (node (ref "CW-LED") (pin "1") (pinfunction "1-G_1") (pintype "unspecified"))
      (node (ref "R21") (pin "2") (pinfunction "2_2") (pintype "unspecified"))
    )
    (net (code "24") (name "Net-(CW-LED-3-R)") (class "Default")
      (node (ref "CW-LED") (pin "3") (pinfunction "3-R_3") (pintype "unspecified"))
      (node (ref "R20") (pin "1") (pinfunction "1_1") (pintype "unspecified"))
    )
    (net (code "25") (name "Net-(F1-Pad1)") (class "Default")
      (node (ref "F1") (pin "1") (pinfunction "1_1") (pintype "unspecified"))
      (node (ref "K1") (pin "4") (pinfunction "4_4") (pintype "unspecified"))
      (node (ref "K1") (pin "5") (pinfunction "5_5") (pintype "unspecified"))
    )
    (net (code "26") (name "Net-(F1-Pad2)") (class "Default")
      (node (ref "F1") (pin "2") (pinfunction "2_2") (pintype "unspecified"))
      (node (ref "LP2") (pin "1") (pinfunction "1_1") (pintype "unspecified"))
    )
    (net (code "27") (name "Net-(HEP-LED-Pad1)") (class "Default")
      (node (ref "HEP-LED") (pin "1") (pinfunction "1_1") (pintype "unspecified"))
      (node (ref "R29") (pin "2") (pinfunction "2_2") (pintype "unspecified"))
    )
    (net (code "28") (name "Net-(HVA-LED-GND)") (class "Default")
      (node (ref "HVA-LED") (pin "1") (pinfunction "GND_1") (pintype "unspecified"))
      (node (ref "R26") (pin "2") (pinfunction "2_2") (pintype "unspecified"))
    )
    (net (code "29") (name "Net-(HVA-LED-VCC)") (class "Default")
      (node (ref "HVA-LED") (pin "3") (pinfunction "VCC_3") (pintype "unspecified"))
      (node (ref "R27") (pin "1") (pinfunction "1_1") (pintype "unspecified"))
    )
    (net (code "30") (name "Net-(HW-LED-1-G)") (class "Default")
      (node (ref "HW-LED") (pin "1") (pinfunction "1-G_1") (pintype "unspecified"))
      (node (ref "R23") (pin "2") (pinfunction "2_2") (pintype "unspecified"))
    )
    (net (code "31") (name "Net-(HW-LED-3-R)") (class "Default")
      (node (ref "HW-LED") (pin "3") (pinfunction "3-R_3") (pintype "unspecified"))
      (node (ref "R22") (pin "1") (pinfunction "1_1") (pintype "unspecified"))
    )
    (net (code "32") (name "Net-(LP1-2)") (class "Default")
      (node (ref "K1") (pin "3") (pinfunction "3_3") (pintype "unspecified"))
      (node (ref "K1") (pin "6") (pinfunction "6_6") (pintype "unspecified"))
      (node (ref "LP1") (pin "1") (pinfunction "2_1") (pintype "unspecified"))
    )
    (net (code "33") (name "Net-(LSE1-Pad2)") (class "Default")
      (node (ref "LSE1") (pin "2") (pinfunction "2_2") (pintype "unspecified"))
      (node (ref "R17") (pin "1") (pinfunction "1_1") (pintype "unspecified"))
    )
    (net (code "34") (name "Net-(LSE2-Pad2)") (class "Default")
      (node (ref "LSE2") (pin "2") (pinfunction "2_2") (pintype "unspecified"))
      (node (ref "R14") (pin "1") (pinfunction "1_1") (pintype "unspecified"))
    )
    (net (code "35") (name "Net-(PH1-Pad1)") (class "Default")
      (node (ref "PH1") (pin "1") (pinfunction "1_1") (pintype "unspecified"))
      (node (ref "R30") (pin "1") (pinfunction "1_1") (pintype "unspecified"))
    )
    (net (code "36") (name "Net-(PH1-Pad3)") (class "Default")
      (node (ref "PH1") (pin "3") (pinfunction "3_3") (pintype "unspecified"))
      (node (ref "R31") (pin "1") (pinfunction "1_1") (pintype "unspecified"))
    )
    (net (code "37") (name "Net-(PWR-IN-GND)") (class "Default")
      (node (ref "D1") (pin "2") (pinfunction "2_2") (pintype "unspecified"))
      (node (ref "PWR-IN") (pin "1") (pinfunction "GND_1") (pintype "unspecified"))
    )
    (net (code "38") (name "Net-(PWR-LED-GRN)") (class "Default")
      (node (ref "PWR-LED") (pin "2") (pinfunction "GRN_2") (pintype "unspecified"))
      (node (ref "R1") (pin "2") (pinfunction "2_2") (pintype "unspecified"))
    )
    (net (code "39") (name "Net-(Q1-B)") (class "Default")
      (node (ref "Q1") (pin "1") (pinfunction "B_1") (pintype "unspecified"))
      (node (ref "R2") (pin "2") (pinfunction "2_2") (pintype "unspecified"))
    )
    (net (code "40") (name "Net-(Q2-B)") (class "Default")
      (node (ref "Q2") (pin "1") (pinfunction "B_1") (pintype "input"))
      (node (ref "R15") (pin "2") (pinfunction "2_2") (pintype "unspecified"))
    )
    (net (code "41") (name "Net-(Q3-B)") (class "Default")
      (node (ref "Q3") (pin "1") (pinfunction "B_1") (pintype "input"))
      (node (ref "R18") (pin "2") (pinfunction "2_2") (pintype "unspecified"))
    )
    (net (code "42") (name "Net-(Q4-D)") (class "Default")
      (node (ref "D3") (pin "1") (pinfunction "1_1") (pintype "unspecified"))
      (node (ref "K1") (pin "8") (pinfunction "8_8") (pintype "input"))
      (node (ref "Q4") (pin "3") (pinfunction "D_3") (pintype "bidirectional"))
    )
    (net (code "43") (name "Net-(Q4-G)") (class "Default")
      (node (ref "Q4") (pin "1") (pinfunction "G_1") (pintype "bidirectional"))
      (node (ref "R31") (pin "2") (pinfunction "2_2") (pintype "unspecified"))
      (node (ref "R39") (pin "1") (pinfunction "1_1") (pintype "unspecified"))
    )
    (net (code "44") (name "Net-(Q5-B)") (class "Default")
      (node (ref "Q5") (pin "1") (pinfunction "B_1") (pintype "unspecified"))
      (node (ref "R28") (pin "2") (pinfunction "2_2") (pintype "unspecified"))
    )
    (net (code "45") (name "Net-(Q5-C)") (class "Default")
      (node (ref "HEP-LED") (pin "2") (pinfunction "2_2") (pintype "unspecified"))
      (node (ref "PH1") (pin "2") (pinfunction "2_2") (pintype "unspecified"))
      (node (ref "Q5") (pin "3") (pinfunction "C_3") (pintype "unspecified"))
    )
    (net (code "46") (name "Net-(U4-OUT1)") (class "Default")
      (node (ref "R23") (pin "1") (pinfunction "1_1") (pintype "unspecified"))
      (node (ref "U4") (pin "18") (pinfunction "OUT1_18") (pintype "output"))
      (node (ref "VALVES") (pin "1") (pinfunction "H-VAL-O_1") (pintype "output"))
    )
    (net (code "47") (name "Net-(U4-OUT2)") (class "Default")
      (node (ref "R22") (pin "2") (pinfunction "2_2") (pintype "unspecified"))
      (node (ref "U4") (pin "17") (pinfunction "OUT2_17") (pintype "output"))
      (node (ref "VALVES") (pin "2") (pinfunction "H-VAL-C_2") (pintype "output"))
    )
    (net (code "48") (name "Net-(U4-OUT3)") (class "Default")
      (node (ref "R21") (pin "1") (pinfunction "1_1") (pintype "unspecified"))
      (node (ref "U4") (pin "14") (pinfunction "OUT3_14") (pintype "output"))
      (node (ref "VALVES") (pin "4") (pinfunction "C-VAL-O_4") (pintype "output"))
    )
    (net (code "49") (name "Net-(U4-OUT4)") (class "Default")
      (node (ref "R20") (pin "2") (pinfunction "2_2") (pintype "unspecified"))
      (node (ref "U4") (pin "13") (pinfunction "OUT4_13") (pintype "output"))
      (node (ref "VALVES") (pin "5") (pinfunction "C-VAL-C_5") (pintype "output"))
    )
    (net (code "50") (name "Net-(U7-OUT)") (class "Default")
      (node (ref "HVALVE") (pin "3") (pinfunction "3_3") (pintype "unspecified"))
      (node (ref "R26") (pin "1") (pinfunction "1_1") (pintype "unspecified"))
      (node (ref "U7") (pin "5") (pinfunction "OUT_5") (pintype "unspecified"))
    )
    (net (code "51") (name "Net-(U8-OUT)") (class "Default")
      (node (ref "HVALVE") (pin "1") (pinfunction "1_1") (pintype "unspecified"))
      (node (ref "R27") (pin "2") (pinfunction "2_2") (pintype "unspecified"))
      (node (ref "U8") (pin "5") (pinfunction "OUT_5") (pintype "unspecified"))
    )
    (net (code "52") (name "Net-(U9-VBAT)") (class "Default")
      (node (ref "C3") (pin "1") (pinfunction "1_1") (pintype "unspecified"))
      (node (ref "CR1") (pin "1") (pinfunction "1_1") (pintype "input"))
      (node (ref "U9") (pin "14") (pinfunction "VBAT_14") (pintype "unspecified"))
    )
    (net (code "53") (name "OPEN-COLD-W") (class "Default")
      (node (ref "H1") (pin "5") (pinfunction "5_5") (pintype "unspecified"))
      (node (ref "U1") (pin "5") (pinfunction "GP3_5") (pintype "unspecified"))
      (node (ref "U4") (pin "7") (pinfunction "IN3_7") (pintype "input"))
    )
    (net (code "54") (name "OPEN-HEATER-W") (class "Default")
      (node (ref "H1") (pin "9") (pinfunction "9_9") (pintype "unspecified"))
      (node (ref "U1") (pin "9") (pinfunction "GP6_9") (pintype "unspecified"))
      (node (ref "U7") (pin "2") (pinfunction "IN_2") (pintype "unspecified"))
    )
    (net (code "55") (name "OPEN-HOT-W") (class "Default")
      (node (ref "H1") (pin "1") (pinfunction "1_1") (pintype "unspecified"))
      (node (ref "U1") (pin "1") (pinfunction "GP0_1") (pintype "unspecified"))
      (node (ref "U4") (pin "3") (pinfunction "IN1_3") (pintype "input"))
    )
    (net (code "56") (name "RESET-B") (class "Default")
      (node (ref "C10") (pin "2") (pinfunction "2_2") (pintype "unspecified"))
      (node (ref "H2") (pin "11") (pinfunction "30_11") (pintype "unspecified"))
      (node (ref "RESET") (pin "2") (pinfunction "2_2") (pintype "unspecified"))
      (node (ref "U1") (pin "30") (pinfunction "RUN_30") (pintype "unspecified"))
    )
    (net (code "57") (name "SDA0") (class "Default")
      (node (ref "H2") (pin "17") (pinfunction "24_17") (pintype "unspecified"))
      (node (ref "LCD1") (pin "3") (pinfunction "3_3") (pintype "unspecified"))
      (node (ref "R5") (pin "1") (pinfunction "1_1") (pintype "unspecified"))
      (node (ref "U1") (pin "24") (pinfunction "GP18_24") (pintype "unspecified"))
      (node (ref "U9") (pin "15") (pinfunction "SDA_15") (pintype "unspecified"))
    )
    (net (code "58") (name "SLC0") (class "Default")
      (node (ref "H2") (pin "16") (pinfunction "25_16") (pintype "unspecified"))
      (node (ref "LCD1") (pin "2") (pinfunction "2_2") (pintype "unspecified"))
      (node (ref "R4") (pin "1") (pinfunction "1_1") (pintype "unspecified"))
      (node (ref "U1") (pin "25") (pinfunction "GP19_25") (pintype "unspecified"))
      (node (ref "U9") (pin "16") (pinfunction "SCL_16") (pintype "unspecified"))
    )
    (net (code "59") (name "TIMER") (class "Default")
      (node (ref "H1") (pin "14") (pinfunction "14_14") (pintype "unspecified"))
      (node (ref "R3") (pin "1") (pinfunction "1_1") (pintype "unspecified"))
      (node (ref "U1") (pin "14") (pinfunction "GP10_14") (pintype "unspecified"))
      (node (ref "U9") (pin "3") (pinfunction "INT#/SQW_3") (pintype "unspecified"))
    )
    (net (code "60") (name "VCC-B") (class "Default")
      (node (ref "C6") (pin "1") (pinfunction "1_1") (pintype "unspecified"))
      (node (ref "H2") (pin "14") (pinfunction "27_14") (pintype "unspecified"))
      (node (ref "R8") (pin "2") (pinfunction "2_2") (pintype "unspecified"))
      (node (ref "U1") (pin "27") (pinfunction "GP21_27") (pintype "unspecified"))
      (node (ref "VCCO-B") (pin "3") (pinfunction "VCC-B_3") (pintype "unspecified"))
    )
    (net (code "61") (name "VCO-B") (class "Default")
      (node (ref "C7") (pin "1") (pinfunction "1_1") (pintype "unspecified"))
      (node (ref "H2") (pin "12") (pinfunction "29_12") (pintype "unspecified"))
      (node (ref "R9") (pin "2") (pinfunction "2_2") (pintype "unspecified"))
      (node (ref "U1") (pin "29") (pinfunction "GP22_29") (pintype "unspecified"))
      (node (ref "VCCO-B") (pin "2") (pinfunction "VCO-B_2") (pintype "unspecified"))
    )
    (net (code "62") (name "VHC-B") (class "Default")
      (node (ref "C4") (pin "1") (pinfunction "1_1") (pintype "unspecified"))
      (node (ref "H2") (pin "10") (pinfunction "31_10") (pintype "unspecified"))
      (node (ref "R6") (pin "2") (pinfunction "2_2") (pintype "unspecified"))
      (node (ref "U1") (pin "31") (pinfunction "GP26_31") (pintype "unspecified"))
      (node (ref "VHCO-B") (pin "3") (pinfunction "VHC-B_3") (pintype "unspecified"))
    )
    (net (code "63") (name "VHO-B") (class "Default")
      (node (ref "C5") (pin "1") (pinfunction "1_1") (pintype "unspecified"))
      (node (ref "H2") (pin "9") (pinfunction "32_9") (pintype "unspecified"))
      (node (ref "R7") (pin "2") (pinfunction "2_2") (pintype "unspecified"))
      (node (ref "U1") (pin "32") (pinfunction "GP27_32") (pintype "unspecified"))
      (node (ref "VHCO-B") (pin "2") (pinfunction "VHO-B_2") (pintype "unspecified"))
    )
    (net (code "64") (name "unconnected-(BUZZ-C-PAD_1-Pad1)") (class "Default")
      (node (ref "BUZZ-C") (pin "1") (pinfunction "PAD_1_1") (pintype "unspecified"))
    )
    (net (code "65") (name "unconnected-(BUZZ-C-PAD_2-Pad4)") (class "Default")
      (node (ref "BUZZ-C") (pin "4") (pinfunction "PAD_2_4") (pintype "unspecified"))
    )
    (net (code "66") (name "unconnected-(H2-33-Pad8)") (class "Default")
      (node (ref "H2") (pin "8") (pinfunction "33_8") (pintype "unspecified+no_connect"))
    )
    (net (code "67") (name "unconnected-(H2-34-Pad7)") (class "Default")
      (node (ref "H2") (pin "7") (pinfunction "34_7") (pintype "unspecified+no_connect"))
    )
    (net (code "68") (name "unconnected-(H2-35-Pad6)") (class "Default")
      (node (ref "H2") (pin "6") (pinfunction "35_6") (pintype "unspecified+no_connect"))
    )
    (net (code "69") (name "unconnected-(H2-37-Pad4)") (class "Default")
      (node (ref "H2") (pin "4") (pinfunction "37_4") (pintype "unspecified+no_connect"))
    )
    (net (code "70") (name "unconnected-(H2-40-Pad1)") (class "Default")
      (node (ref "H2") (pin "1") (pinfunction "40_1") (pintype "unspecified+no_connect"))
    )
    (net (code "71") (name "unconnected-(K1-Pad2)") (class "Default")
      (node (ref "K1") (pin "2") (pinfunction "2_2") (pintype "unspecified+no_connect"))
    )
    (net (code "72") (name "unconnected-(K1-Pad7)") (class "Default")
      (node (ref "K1") (pin "7") (pinfunction "7_7") (pintype "unspecified+no_connect"))
    )
    (net (code "73") (name "unconnected-(U1-3V3_EN-Pad37)") (class "Default")
      (node (ref "U1") (pin "37") (pinfunction "3V3_EN_37") (pintype "unspecified+no_connect"))
    )
    (net (code "74") (name "unconnected-(U1-ADC_VREF-Pad35)") (class "Default")
      (node (ref "U1") (pin "35") (pinfunction "ADC_VREF_35") (pintype "unspecified+no_connect"))
    )
    (net (code "75") (name "unconnected-(U1-GND-Pad33)") (class "Default")
      (node (ref "U1") (pin "33") (pinfunction "GND_33") (pintype "unspecified+no_connect"))
    )
    (net (code "76") (name "unconnected-(U1-GND-Pad42)") (class "Default")
      (node (ref "U1") (pin "42") (pinfunction "GND_42") (pintype "unspecified+no_connect"))
    )
    (net (code "77") (name "unconnected-(U1-GP28-Pad34)") (class "Default")
      (node (ref "U1") (pin "34") (pinfunction "GP28_34") (pintype "unspecified+no_connect"))
    )
    (net (code "78") (name "unconnected-(U1-PadTP1)") (class "Default")
      (node (ref "U1") (pin "TP1") (pinfunction "TP1_TP1") (pintype "unspecified+no_connect"))
    )
    (net (code "79") (name "unconnected-(U1-PadTP2)") (class "Default")
      (node (ref "U1") (pin "TP2") (pinfunction "TP2_TP2") (pintype "unspecified+no_connect"))
    )
    (net (code "80") (name "unconnected-(U1-PadTP3)") (class "Default")
      (node (ref "U1") (pin "TP3") (pinfunction "TP3_TP3") (pintype "unspecified+no_connect"))
    )
    (net (code "81") (name "unconnected-(U1-PadTP4)") (class "Default")
      (node (ref "U1") (pin "TP4") (pinfunction "TP4_TP4") (pintype "unspecified+no_connect"))
    )
    (net (code "82") (name "unconnected-(U1-PadTP5)") (class "Default")
      (node (ref "U1") (pin "TP5") (pinfunction "TP5_TP5") (pintype "unspecified+no_connect"))
    )
    (net (code "83") (name "unconnected-(U1-PadTP6)") (class "Default")
      (node (ref "U1") (pin "TP6") (pinfunction "TP6_TP6") (pintype "unspecified+no_connect"))
    )
    (net (code "84") (name "unconnected-(U1-SWCLK-Pad41)") (class "Default")
      (node (ref "U1") (pin "41") (pinfunction "SWCLK_41") (pintype "unspecified+no_connect"))
    )
    (net (code "85") (name "unconnected-(U1-SWDIO-Pad43)") (class "Default")
      (node (ref "U1") (pin "43") (pinfunction "SWDIO_43") (pintype "unspecified+no_connect"))
    )
    (net (code "86") (name "unconnected-(U1-VBUS-Pad40)") (class "Default")
      (node (ref "U1") (pin "40") (pinfunction "VBUS_40") (pintype "unspecified+no_connect"))
    )
    (net (code "87") (name "unconnected-(U7-NC-Pad4)") (class "Default")
      (node (ref "U7") (pin "4") (pinfunction "NC_4") (pintype "unspecified+no_connect"))
    )
    (net (code "88") (name "unconnected-(U8-NC-Pad4)") (class "Default")
      (node (ref "U8") (pin "4") (pinfunction "NC_4") (pintype "unspecified+no_connect"))
    )
    (net (code "89") (name "unconnected-(U9-32KHZ-Pad1)") (class "Default")
      (node (ref "U9") (pin "1") (pinfunction "32KHZ_1") (pintype "unspecified+no_connect"))
    )
    (net (code "90") (name "unconnected-(U9-RST#-Pad4)") (class "Default")
      (node (ref "U9") (pin "4") (pinfunction "RST#_4") (pintype "unspecified+no_connect"))
    )
  )
)
